# SparkFun_XBee_Arduino_Shield_Qwiic.net
KiCad netlist of a schematic drawn in EAGLE
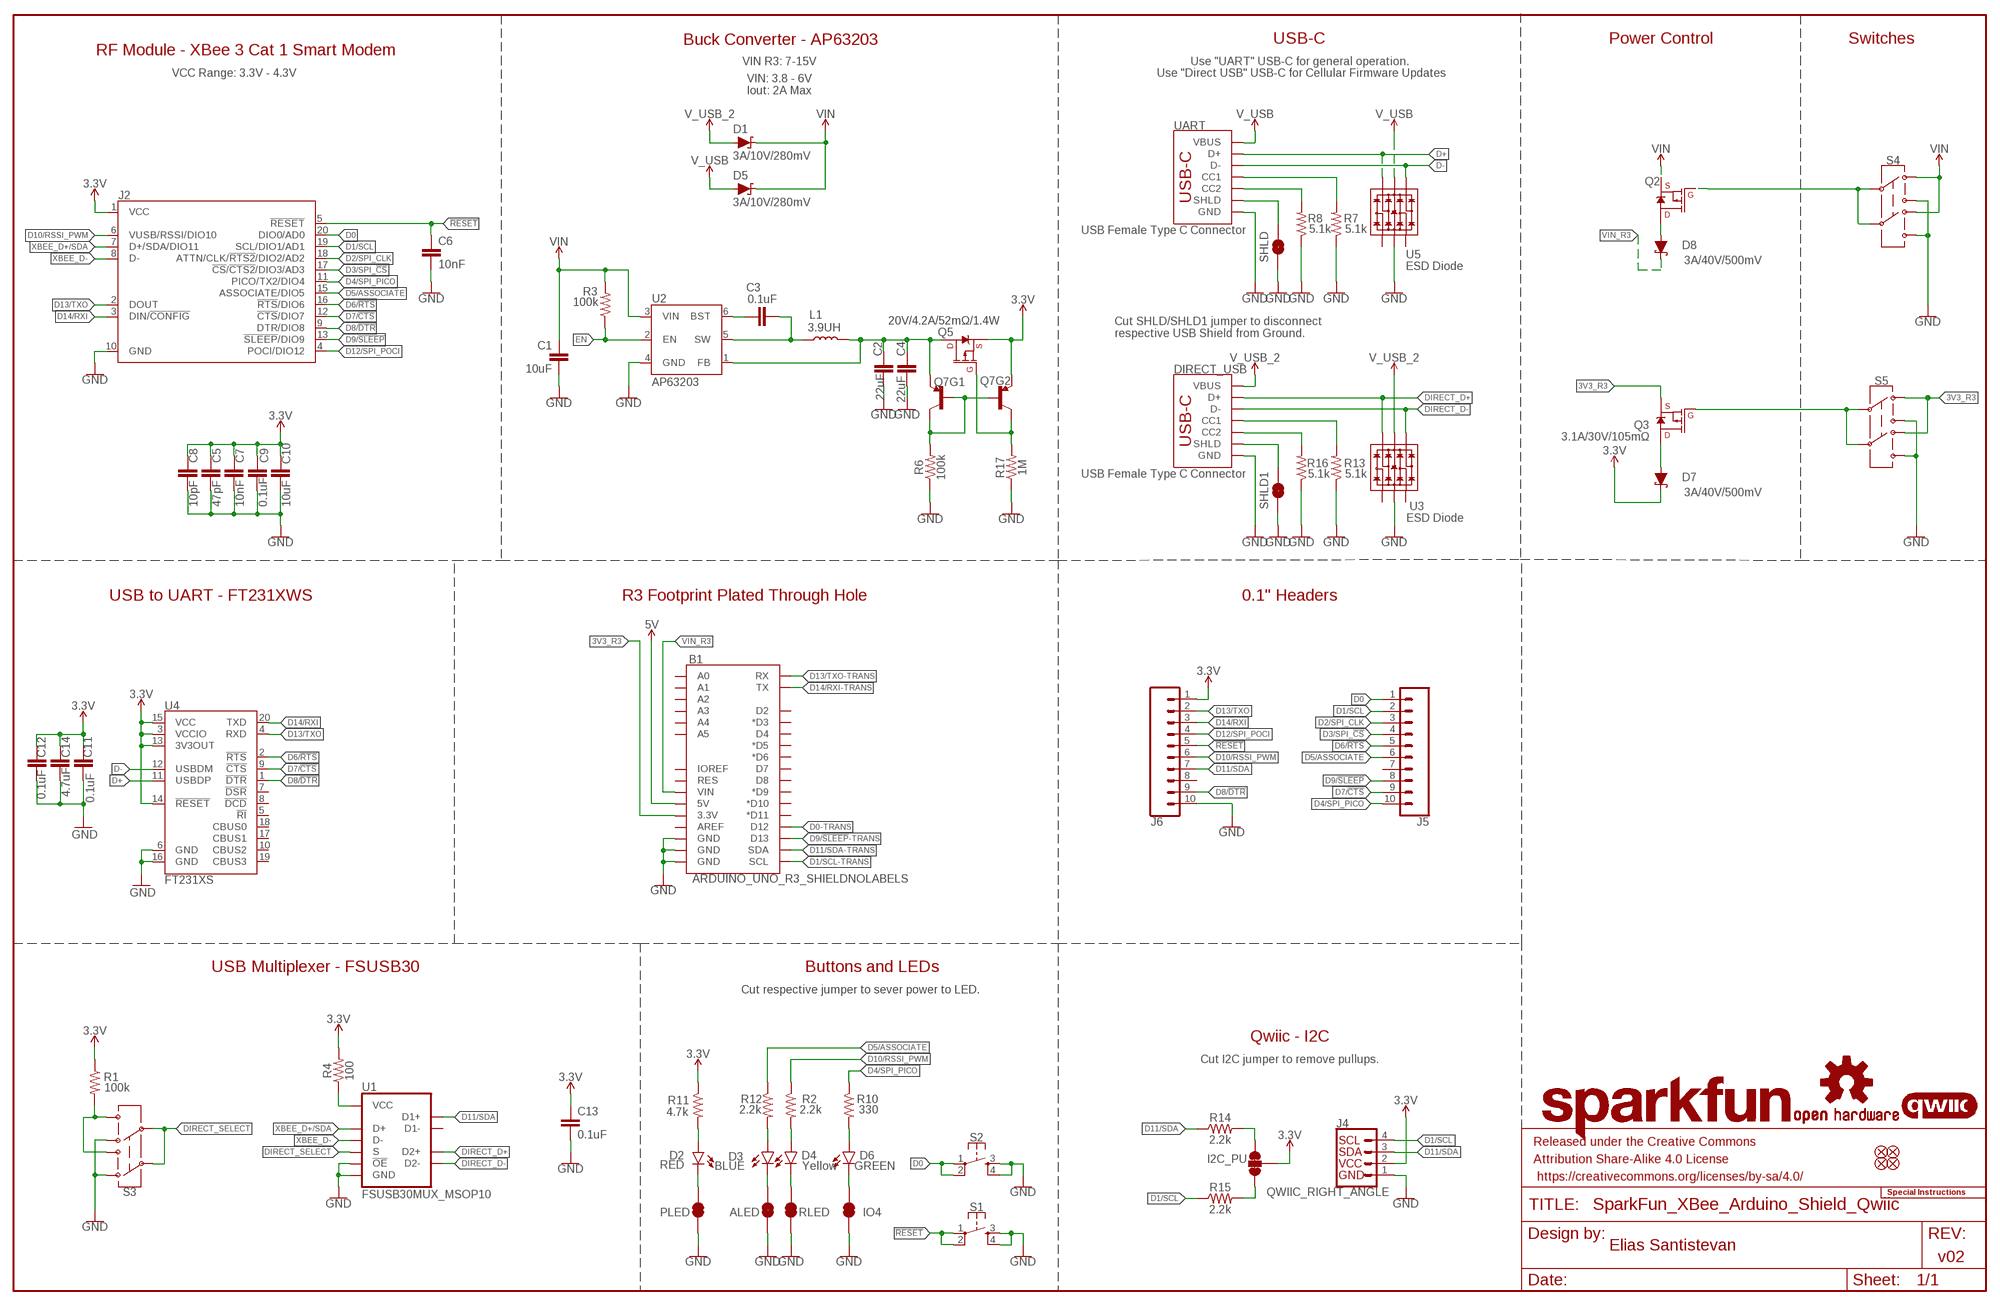
[diagram p0: schematic, sheet 1]

(export (version "E")
  (design (tool "Eeschema 10.0.6"))
  (components
    (comp (ref "ALED")
      (value "JUMPER-SMT_2_NC_TRACE_SILK")
      (footprint "eagle-import:SMT-JUMPER_2_NC_TRACE_SILK")
      (libsource (lib "eagle-import") (part "JUMPER-SMT_2_NC_TRACE_SILK"))
    )
    (comp (ref "B1")
      (value "ARDUINO_UNO_R3_SHIELDNOLABELS")
      (footprint "eagle-import:UNO_R3_SHIELD_NOLABELS")
      (libsource (lib "eagle-import") (part "ARDUINO_UNO_R3_SHIELDNOLABELS"))
    )
    (comp (ref "C1")
      (value "10uF")
      (footprint "eagle-import:1210")
      (libsource (lib "eagle-import") (part "10UF-1210-50V-20%"))
    )
    (comp (ref "C2")
      (value "22uF")
      (footprint "eagle-import:0603")
      (libsource (lib "eagle-import") (part "22UF-0603-6.3V-20%"))
    )
    (comp (ref "C3")
      (value "0.1uF")
      (footprint "eagle-import:0603")
      (libsource (lib "eagle-import") (part "0.1UF-0603-25V-5%"))
    )
    (comp (ref "C4")
      (value "22uF")
      (footprint "eagle-import:0603")
      (libsource (lib "eagle-import") (part "22UF-0603-6.3V-20%"))
    )
    (comp (ref "C5")
      (value "47pF")
      (footprint "eagle-import:0603")
      (libsource (lib "eagle-import") (part "47PF-0603-50V-5%"))
    )
    (comp (ref "C6")
      (value "10nF")
      (footprint "eagle-import:0603")
      (libsource (lib "eagle-import") (part "10NF-0603-50V-10%"))
    )
    (comp (ref "C7")
      (value "10nF")
      (footprint "eagle-import:0603")
      (libsource (lib "eagle-import") (part "10NF-0603-50V-10%"))
    )
    (comp (ref "C8")
      (value "10pF")
      (footprint "eagle-import:0603")
      (libsource (lib "eagle-import") (part "10PF-0603-50V-5%"))
    )
    (comp (ref "C9")
      (value "0.1uF")
      (footprint "eagle-import:0603")
      (libsource (lib "eagle-import") (part "0.1UF-0603-25V-(+80/-20%)"))
    )
    (comp (ref "C10")
      (value "10uF")
      (footprint "eagle-import:0603")
      (libsource (lib "eagle-import") (part "10UF-0603-6.3V-20%"))
    )
    (comp (ref "C11")
      (value "0.1uF")
      (footprint "eagle-import:0603")
      (libsource (lib "eagle-import") (part "0.1UF-0603-25V-(+80/-20%)"))
    )
    (comp (ref "C12")
      (value "0.1uF")
      (footprint "eagle-import:0603")
      (libsource (lib "eagle-import") (part "0.1UF-0603-25V-(+80/-20%)"))
    )
    (comp (ref "C13")
      (value "0.1uF")
      (footprint "eagle-import:0603")
      (libsource (lib "eagle-import") (part "0.1UF-0603-25V-(+80/-20%)"))
    )
    (comp (ref "C14")
      (value "4.7uF")
      (footprint "eagle-import:0603")
      (libsource (lib "eagle-import") (part "4.7UF-0603-6.3V-(10%)"))
    )
    (comp (ref "D1")
      (value "3A/10V/280mV")
      (footprint "eagle-import:SOD-323")
      (libsource (lib "eagle-import") (part "DIODE-SCHOTTKY-BAT60A"))
    )
    (comp (ref "D2")
      (value "RED")
      (footprint "eagle-import:LED-0603")
      (libsource (lib "eagle-import") (part "LED-RED_0603-KB"))
    )
    (comp (ref "D3")
      (value "BLUE")
      (footprint "eagle-import:LED-0603")
      (libsource (lib "eagle-import") (part "LED-BLUE0603"))
    )
    (comp (ref "D4")
      (value "Yellow")
      (footprint "eagle-import:LED-0603")
      (libsource (lib "eagle-import") (part "LED-YELLOW0603"))
    )
    (comp (ref "D5")
      (value "3A/10V/280mV")
      (footprint "eagle-import:SOD-323")
      (libsource (lib "eagle-import") (part "DIODE-SCHOTTKY-BAT60A"))
    )
    (comp (ref "D6")
      (value "GREEN")
      (footprint "eagle-import:LED-0603")
      (libsource (lib "eagle-import") (part "LED-GREEN0603"))
    )
    (comp (ref "D7")
      (value "3A/40V/500mV")
      (footprint "eagle-import:SMA-DIODE")
      (libsource (lib "eagle-import") (part "DIODE-SCHOTTKY-B340A"))
    )
    (comp (ref "D8")
      (value "3A/40V/500mV")
      (footprint "eagle-import:SMA-DIODE")
      (libsource (lib "eagle-import") (part "DIODE-SCHOTTKY-B340A"))
    )
    (comp (ref "DIRECT_USB")
      (value "USB Female Type C Connector")
      (footprint "eagle-import:USB-C-16P-4LAYER-ISOLATED")
      (libsource (lib "eagle-import") (part "USB_C_4-LAYER-ISOLATED"))
    )
    (comp (ref "FD1")
      (value "FIDUCIAL1X2")
      (footprint "eagle-import:FIDUCIAL-1X2")
      (libsource (lib "eagle-import") (part "FIDUCIAL1X2"))
    )
    (comp (ref "FD2")
      (value "FIDUCIAL1X2")
      (footprint "eagle-import:FIDUCIAL-1X2")
      (libsource (lib "eagle-import") (part "FIDUCIAL1X2"))
    )
    (comp (ref "FD3")
      (value "FIDUCIAL1X2")
      (footprint "eagle-import:FIDUCIAL-1X2")
      (libsource (lib "eagle-import") (part "FIDUCIAL1X2"))
    )
    (comp (ref "FD4")
      (value "FIDUCIAL1X2")
      (footprint "eagle-import:FIDUCIAL-1X2")
      (libsource (lib "eagle-import") (part "FIDUCIAL1X2"))
    )
    (comp (ref "FRAME1")
      (value "FRAME-LEDGER")
      (footprint "eagle-import:CREATIVE_COMMONS")
      (libsource (lib "eagle-import") (part "FRAME-LEDGER"))
    )
    (comp (ref "I2C_PU")
      (value "JUMPER-SMT_3_2-NC_TRACE_SILK")
      (footprint "eagle-import:SMT-JUMPER_3_2-NC_TRACE_SILK")
      (libsource (lib "eagle-import") (part "JUMPER-SMT_3_2-NC_TRACE_SILK"))
    )
    (comp (ref "IO4")
      (value "JUMPER-SMT_2_NC_TRACE_SILK")
      (footprint "eagle-import:SMT-JUMPER_2_NC_TRACE_SILK")
      (libsource (lib "eagle-import") (part "JUMPER-SMT_2_NC_TRACE_SILK"))
    )
    (comp (ref "J2")
      (value "XBEE_UPDATEXBEE_SMD")
      (footprint "eagle-import:XBEE3-SMD")
      (libsource (lib "eagle-import") (part "XBEE_UPDATEXBEE_SMD"))
    )
    (comp (ref "J4")
      (value "QWIIC_RIGHT_ANGLE")
      (footprint "eagle-import:JST04_1MM_RA")
      (libsource (lib "eagle-import") (part "QWIIC_CONNECTORJS-1MM"))
    )
    (comp (ref "J5")
      (value "CONN_10NO_SILK_PTH_FEMALE")
      (footprint "eagle-import:1X10_NO_SILK")
      (libsource (lib "eagle-import") (part "CONN_10NO_SILK_PTH_FEMALE"))
    )
    (comp (ref "J6")
      (value "CONN_10NO_SILK_PTH_FEMALE")
      (footprint "eagle-import:1X10_NO_SILK")
      (libsource (lib "eagle-import") (part "CONN_10NO_SILK_PTH_FEMALE"))
    )
    (comp (ref "L1")
      (value "3.9UH")
      (footprint "eagle-import:INDUCTOR_3.9UH")
      (libsource (lib "eagle-import") (part "3.9UH"))
    )
    (comp (ref "LOGO1")
      (value "SFE_LOGO_NAMEBLANK")
      (footprint "eagle-import:BLANK")
      (libsource (lib "eagle-import") (part "SFE_LOGO_NAMEBLANK"))
    )
    (comp (ref "LOGO2")
      (value "OSHW-LOGOS")
      (footprint "eagle-import:OSHW-LOGO-S")
      (libsource (lib "eagle-import") (part "OSHW-LOGOS"))
    )
    (comp (ref "LOGO3")
      (value "QWIIC_LOGO_4MM")
      (footprint "eagle-import:QWIIC_4MM")
      (libsource (lib "eagle-import") (part "QWIIC_LOGO_4MM"))
    )
    (comp (ref "LOGO4")
      (value "SPECIAL_INSTRUCTIONS-ORDERING")
      (footprint "eagle-import:ORDERING_INSTRUCTIONS")
      (libsource (lib "eagle-import") (part "SPECIAL_INSTRUCTIONS-ORDERING"))
    )
    (comp (ref "PLED")
      (value "JUMPER-SMT_2_NC_TRACE_SILK")
      (footprint "eagle-import:SMT-JUMPER_2_NC_TRACE_SILK")
      (libsource (lib "eagle-import") (part "JUMPER-SMT_2_NC_TRACE_SILK"))
    )
    (comp (ref "Q2")
      (value "20V/4.2A/52mΩ/1.4W")
      (footprint "eagle-import:SOT23-3")
      (libsource (lib "eagle-import") (part "MOSFET_PCH-DMG2305UX-7"))
    )
    (comp (ref "Q3")
      (value "3.1A/30V/105mΩ")
      (footprint "eagle-import:SOT23-3")
      (libsource (lib "eagle-import") (part "MOSFET_PCH-DMG2307L"))
    )
    (comp (ref "Q5")
      (value "20V/4.2A/52mΩ/1.4W")
      (footprint "eagle-import:SOT23-3")
      (libsource (lib "eagle-import") (part "MOSFET_PCH-DMG2305UX-7"))
    )
    (comp (ref "Q7")
      (value "TRANS_PNP_DUALSOT-363")
      (footprint "eagle-import:SOT363_PHILIPS")
      (libsource (lib "eagle-import") (part "TRANS_PNP_DUALSOT-363"))
    )
    (comp (ref "R1")
      (value "100k")
      (footprint "eagle-import:0603")
      (libsource (lib "eagle-import") (part "100KOHM-0603-1/10W-1%"))
    )
    (comp (ref "R2")
      (value "2.2k")
      (footprint "eagle-import:0603")
      (libsource (lib "eagle-import") (part "2.2KOHM-0603-1/10W-1%"))
    )
    (comp (ref "R3")
      (value "100k")
      (footprint "eagle-import:0603")
      (libsource (lib "eagle-import") (part "100KOHM-0603-1/10W-1%"))
    )
    (comp (ref "R4")
      (value "100")
      (footprint "eagle-import:0603")
      (libsource (lib "eagle-import") (part "100OHM-0603-1/10W-1%"))
    )
    (comp (ref "R6")
      (value "100k")
      (footprint "eagle-import:0603")
      (libsource (lib "eagle-import") (part "100KOHM-0603-1/10W-1%"))
    )
    (comp (ref "R7")
      (value "5.1k")
      (footprint "eagle-import:0603")
      (libsource (lib "eagle-import") (part "5.1KOHM5.1KOHM-0603-1/10W-1%"))
    )
    (comp (ref "R8")
      (value "5.1k")
      (footprint "eagle-import:0603")
      (libsource (lib "eagle-import") (part "5.1KOHM5.1KOHM-0603-1/10W-1%"))
    )
    (comp (ref "R10")
      (value "330")
      (footprint "eagle-import:0603")
      (libsource (lib "eagle-import") (part "330OHM-0603-1/10W-1%"))
    )
    (comp (ref "R11")
      (value "4.7k")
      (footprint "eagle-import:0603")
      (libsource (lib "eagle-import") (part "4.7KOHM-0603-1/10W-1%"))
    )
    (comp (ref "R12")
      (value "2.2k")
      (footprint "eagle-import:0603")
      (libsource (lib "eagle-import") (part "2.2KOHM-0603-1/10W-1%"))
    )
    (comp (ref "R13")
      (value "5.1k")
      (footprint "eagle-import:0603")
      (libsource (lib "eagle-import") (part "5.1KOHM5.1KOHM-0603-1/10W-1%"))
    )
    (comp (ref "R14")
      (value "2.2k")
      (footprint "eagle-import:0603")
      (libsource (lib "eagle-import") (part "2.2KOHM-0603-1/10W-1%"))
    )
    (comp (ref "R15")
      (value "2.2k")
      (footprint "eagle-import:0603")
      (libsource (lib "eagle-import") (part "2.2KOHM-0603-1/10W-1%"))
    )
    (comp (ref "R16")
      (value "5.1k")
      (footprint "eagle-import:0603")
      (libsource (lib "eagle-import") (part "5.1KOHM5.1KOHM-0603-1/10W-1%"))
    )
    (comp (ref "R17")
      (value "1M")
      (footprint "eagle-import:0603")
      (libsource (lib "eagle-import") (part "1MOHM-0603-1/4W-5%"))
    )
    (comp (ref "RLED")
      (value "JUMPER-SMT_2_NC_TRACE_SILK")
      (footprint "eagle-import:SMT-JUMPER_2_NC_TRACE_SILK")
      (libsource (lib "eagle-import") (part "JUMPER-SMT_2_NC_TRACE_SILK"))
    )
    (comp (ref "S1")
      (value "MOMENTARY-SWITCH-SPST-2-SMD-5.2MM-TALL")
      (footprint "eagle-import:TACTILE_SWITCH_SMD_5.2MM")
      (libsource (lib "eagle-import") (part "MOMENTARY-SWITCH-SPST-2-SMD-5.2MM-TALL"))
    )
    (comp (ref "S2")
      (value "MOMENTARY-SWITCH-SPST-2-SMD-5.2MM-TALL")
      (footprint "eagle-import:TACTILE_SWITCH_SMD_5.2MM")
      (libsource (lib "eagle-import") (part "MOMENTARY-SWITCH-SPST-2-SMD-5.2MM-TALL"))
    )
    (comp (ref "S3")
      (value "SWITCH-DPDT-SMD-AYZ0202")
      (footprint "eagle-import:SWITCH_DPDT_SMD_AYZ0202")
      (libsource (lib "eagle-import") (part "SWITCH-DPDT-SMD-AYZ0202"))
    )
    (comp (ref "S4")
      (value "SWITCH-DPDT-SMD-AYZ0202")
      (footprint "eagle-import:SWITCH_DPDT_SMD_AYZ0202")
      (libsource (lib "eagle-import") (part "SWITCH-DPDT-SMD-AYZ0202"))
    )
    (comp (ref "S5")
      (value "SWITCH-DPDT-SMD-AYZ0202")
      (footprint "eagle-import:SWITCH_DPDT_SMD_AYZ0202")
      (libsource (lib "eagle-import") (part "SWITCH-DPDT-SMD-AYZ0202"))
    )
    (comp (ref "SHLD")
      (value "JUMPER-SMT_2_NC_TRACE_SILK")
      (footprint "eagle-import:SMT-JUMPER_2_NC_TRACE_SILK")
      (libsource (lib "eagle-import") (part "JUMPER-SMT_2_NC_TRACE_SILK"))
    )
    (comp (ref "SHLD1")
      (value "JUMPER-SMT_2_NC_TRACE_SILK")
      (footprint "eagle-import:SMT-JUMPER_2_NC_TRACE_SILK")
      (libsource (lib "eagle-import") (part "JUMPER-SMT_2_NC_TRACE_SILK"))
    )
    (comp (ref "U1")
      (value "FSUSB30MUX_MSOP10")
      (footprint "eagle-import:MSOP10")
      (libsource (lib "eagle-import") (part "FSUSB30MUX_MSOP10"))
    )
    (comp (ref "U2")
      (value "AP63203")
      (footprint "eagle-import:SOT23-6")
      (libsource (lib "eagle-import") (part "AP63203"))
    )
    (comp (ref "U3")
      (value "ESD Diode")
      (footprint "eagle-import:SOT-23-6")
      (libsource (lib "eagle-import") (part "TVS_DIODE_ARRAY_DT1042-04SO-7"))
    )
    (comp (ref "U4")
      (value "FT231XS")
      (footprint "eagle-import:SSOP20_L")
      (libsource (lib "eagle-import") (part "FT231XS"))
    )
    (comp (ref "U5")
      (value "ESD Diode")
      (footprint "eagle-import:SOT-23-6")
      (libsource (lib "eagle-import") (part "TVS_DIODE_ARRAY_DT1042-04SO-7"))
    )
    (comp (ref "UART")
      (value "USB Female Type C Connector")
      (footprint "eagle-import:USB-C-16P-4LAYER-ISOLATED")
      (libsource (lib "eagle-import") (part "USB_C_4-LAYER-ISOLATED"))
    )
  )
  (nets
    (net (code "1") (name "/D3{slash}SPI_~{CS}") (class "Default")
      (node (ref "J2") (pin "17") (pinfunction "~{CS}/~{CTS2}/DIO3/AD3_17") (pintype "bidirectional"))
      (node (ref "J5") (pin "4") (pinfunction "4_4") (pintype "passive"))
    )
    (net (code "2") (name "/D6{slash}~{RTS}") (class "Default")
      (node (ref "J2") (pin "16") (pinfunction "~{RTS}/DIO6_16") (pintype "input"))
      (node (ref "J5") (pin "5") (pinfunction "5_5") (pintype "passive"))
      (node (ref "U4") (pin "2") (pinfunction "~{RTS}_2") (pintype "bidirectional"))
    )
    (net (code "3") (name "/D7{slash}~{CTS}") (class "Default")
      (node (ref "J2") (pin "12") (pinfunction "~{CTS}/DIO7_12") (pintype "output"))
      (node (ref "J5") (pin "9") (pinfunction "9_9") (pintype "passive"))
      (node (ref "U4") (pin "9") (pinfunction "~{CTS}_9") (pintype "bidirectional"))
    )
    (net (code "4") (name "/D8{slash}~{DTR}") (class "Default")
      (node (ref "J2") (pin "9") (pinfunction "DTR/DIO8_9") (pintype "bidirectional"))
      (node (ref "J6") (pin "9") (pinfunction "9_9") (pintype "passive"))
      (node (ref "U4") (pin "1") (pinfunction "~{DTR}_1") (pintype "bidirectional"))
    )
    (net (code "5") (name "/D9{slash}~{SLEEP}") (class "Default")
      (node (ref "J2") (pin "13") (pinfunction "~{SLEEP}/DIO9_13") (pintype "bidirectional"))
      (node (ref "J5") (pin "8") (pinfunction "8_8") (pintype "passive"))
    )
    (net (code "6") (name "/D9{slash}~{SLEEP}-TRANS") (class "Default")
      (node (ref "B1") (pin "D13") (pinfunction "D13_D13") (pintype "bidirectional"))
    )
    (net (code "7") (name "/~{RESET}") (class "Default")
      (node (ref "C6") (pin "1") (pinfunction "1_1") (pintype "passive"))
      (node (ref "J2") (pin "5") (pinfunction "~{RESET}_5") (pintype "input"))
      (node (ref "J6") (pin "5") (pinfunction "5_5") (pintype "passive"))
      (node (ref "S1") (pin "1") (pinfunction "1_1") (pintype "passive"))
      (node (ref "S1") (pin "2") (pinfunction "2_2") (pintype "passive"))
    )
    (net (code "8") (name "3.3V") (class "Default")
      (node (ref "C10") (pin "1") (pinfunction "1_1") (pintype "passive"))
      (node (ref "C11") (pin "1") (pinfunction "1_1") (pintype "passive"))
      (node (ref "C12") (pin "1") (pinfunction "1_1") (pintype "passive"))
      (node (ref "C13") (pin "1") (pinfunction "1_1") (pintype "passive"))
      (node (ref "C14") (pin "1") (pinfunction "1_1") (pintype "passive"))
      (node (ref "C5") (pin "1") (pinfunction "1_1") (pintype "passive"))
      (node (ref "C7") (pin "1") (pinfunction "1_1") (pintype "passive"))
      (node (ref "C8") (pin "1") (pinfunction "1_1") (pintype "passive"))
      (node (ref "C9") (pin "1") (pinfunction "1_1") (pintype "passive"))
      (node (ref "D7") (pin "C") (pinfunction "C_C") (pintype "passive"))
      (node (ref "I2C_PU") (pin "2") (pinfunction "2_2") (pintype "passive"))
      (node (ref "J2") (pin "1") (pinfunction "VCC_1") (pintype "power_in"))
      (node (ref "J4") (pin "2") (pinfunction "2_2") (pintype "power_in"))
      (node (ref "J6") (pin "1") (pinfunction "1_1") (pintype "passive"))
      (node (ref "Q5") (pin "2") (pinfunction "S_2") (pintype "bidirectional"))
      (node (ref "Q7") (pin "4") (pinfunction "E_4") (pintype "passive"))
      (node (ref "R1") (pin "1") (pinfunction "1_1") (pintype "passive"))
      (node (ref "R11") (pin "1") (pinfunction "1_1") (pintype "passive"))
      (node (ref "R4") (pin "2") (pinfunction "2_2") (pintype "passive"))
      (node (ref "U4") (pin "13") (pinfunction "3V3OUT_13") (pintype "bidirectional"))
      (node (ref "U4") (pin "14") (pinfunction "~{RESET}_14") (pintype "bidirectional"))
      (node (ref "U4") (pin "15") (pinfunction "VCC_15") (pintype "bidirectional"))
      (node (ref "U4") (pin "3") (pinfunction "VCCIO_3") (pintype "bidirectional"))
    )
    (net (code "9") (name "3V3_R3") (class "Default")
      (node (ref "B1") (pin "3.3V") (pinfunction "3.3V_3.3V") (pintype "bidirectional"))
      (node (ref "Q3") (pin "2") (pinfunction "S_2") (pintype "bidirectional"))
      (node (ref "S5") (pin "3") (pinfunction "3_3") (pintype "bidirectional"))
      (node (ref "S5") (pin "6") (pinfunction "6_6") (pintype "bidirectional"))
    )
    (net (code "10") (name "5V") (class "Default")
      (node (ref "B1") (pin "5V") (pinfunction "5V_5V") (pintype "bidirectional"))
    )
    (net (code "11") (name "D+") (class "Default")
      (node (ref "U4") (pin "11") (pinfunction "USBDP_11") (pintype "bidirectional"))
      (node (ref "U5") (pin "6") (pinfunction "IO4_6") (pintype "bidirectional"))
      (node (ref "UART") (pin "A6") (pinfunction "D+_A6") (pintype "bidirectional"))
      (node (ref "UART") (pin "B6") (pinfunction "D+_B6") (pintype "bidirectional"))
    )
    (net (code "12") (name "D-") (class "Default")
      (node (ref "U4") (pin "12") (pinfunction "USBDM_12") (pintype "bidirectional"))
      (node (ref "U5") (pin "4") (pinfunction "IO3_4") (pintype "bidirectional"))
      (node (ref "UART") (pin "A7") (pinfunction "D-_A7") (pintype "bidirectional"))
      (node (ref "UART") (pin "B7") (pinfunction "D-_B7") (pintype "bidirectional"))
    )
    (net (code "13") (name "D0") (class "Default")
      (node (ref "J2") (pin "20") (pinfunction "DIO0/AD0_20") (pintype "bidirectional"))
      (node (ref "J5") (pin "1") (pinfunction "1_1") (pintype "passive"))
      (node (ref "S2") (pin "1") (pinfunction "1_1") (pintype "passive"))
      (node (ref "S2") (pin "2") (pinfunction "2_2") (pintype "passive"))
    )
    (net (code "14") (name "D0-TRANS") (class "Default")
      (node (ref "B1") (pin "D12") (pinfunction "D12_D12") (pintype "bidirectional"))
    )
    (net (code "15") (name "D1{slash}SCL") (class "Default")
      (node (ref "J2") (pin "19") (pinfunction "SCL/DIO1/AD1_19") (pintype "bidirectional"))
      (node (ref "J4") (pin "4") (pinfunction "4_4") (pintype "passive"))
      (node (ref "J5") (pin "2") (pinfunction "2_2") (pintype "passive"))
      (node (ref "R15") (pin "1") (pinfunction "1_1") (pintype "passive"))
    )
    (net (code "16") (name "D1{slash}SCL-TRANS") (class "Default")
      (node (ref "B1") (pin "SCL") (pinfunction "SCL_SCL") (pintype "bidirectional"))
    )
    (net (code "17") (name "D2{slash}SPI_CLK") (class "Default")
      (node (ref "J2") (pin "18") (pinfunction "ATTN/CLK/~{RTS2}/DIO2/AD2_18") (pintype "bidirectional"))
      (node (ref "J5") (pin "3") (pinfunction "3_3") (pintype "passive"))
    )
    (net (code "18") (name "D4{slash}SPI_PICO") (class "Default")
      (node (ref "J2") (pin "11") (pinfunction "PICO/TX2/DIO4_11") (pintype "bidirectional"))
      (node (ref "J5") (pin "10") (pinfunction "10_10") (pintype "passive"))
      (node (ref "R10") (pin "1") (pinfunction "1_1") (pintype "passive"))
    )
    (net (code "19") (name "D5{slash}ASSOCIATE") (class "Default")
      (node (ref "J2") (pin "15") (pinfunction "ASSOCIATE/DIO5_15") (pintype "bidirectional"))
      (node (ref "J5") (pin "6") (pinfunction "6_6") (pintype "passive"))
      (node (ref "R12") (pin "1") (pinfunction "1_1") (pintype "passive"))
    )
    (net (code "20") (name "D10{slash}RSSI_PWM") (class "Default")
      (node (ref "J2") (pin "6") (pinfunction "VUSB/RSSI/DIO10_6") (pintype "bidirectional"))
      (node (ref "J6") (pin "6") (pinfunction "6_6") (pintype "passive"))
      (node (ref "R2") (pin "1") (pinfunction "1_1") (pintype "passive"))
    )
    (net (code "21") (name "D11{slash}SDA") (class "Default")
      (node (ref "J4") (pin "3") (pinfunction "3_3") (pintype "passive"))
      (node (ref "J6") (pin "7") (pinfunction "7_7") (pintype "passive"))
      (node (ref "R14") (pin "1") (pinfunction "1_1") (pintype "passive"))
      (node (ref "U1") (pin "2") (pinfunction "D1+_2") (pintype "bidirectional"))
    )
    (net (code "22") (name "D11{slash}SDA-TRANS") (class "Default")
      (node (ref "B1") (pin "SDA") (pinfunction "SDA_SDA") (pintype "bidirectional"))
    )
    (net (code "23") (name "D12{slash}SPI_POCI") (class "Default")
      (node (ref "J2") (pin "4") (pinfunction "POCI/DIO12_4") (pintype "bidirectional"))
      (node (ref "J6") (pin "4") (pinfunction "4_4") (pintype "passive"))
    )
    (net (code "24") (name "D13{slash}TXO") (class "Default")
      (node (ref "J2") (pin "2") (pinfunction "DOUT_2") (pintype "output"))
      (node (ref "J6") (pin "2") (pinfunction "2_2") (pintype "passive"))
      (node (ref "U4") (pin "4") (pinfunction "RXD_4") (pintype "bidirectional"))
    )
    (net (code "25") (name "D13{slash}TXO-TRANS") (class "Default")
      (node (ref "B1") (pin "RX") (pinfunction "RX_RX") (pintype "bidirectional"))
    )
    (net (code "26") (name "D14{slash}RXI") (class "Default")
      (node (ref "J2") (pin "3") (pinfunction "DIN/~{CONFIG}_3") (pintype "input"))
      (node (ref "J6") (pin "3") (pinfunction "3_3") (pintype "passive"))
      (node (ref "U4") (pin "20") (pinfunction "TXD_20") (pintype "bidirectional"))
    )
    (net (code "27") (name "D14{slash}RXI-TRANS") (class "Default")
      (node (ref "B1") (pin "TX") (pinfunction "TX_TX") (pintype "bidirectional"))
    )
    (net (code "28") (name "DIRECT_D+") (class "Default")
      (node (ref "DIRECT_USB") (pin "A6") (pinfunction "D+_A6") (pintype "bidirectional"))
      (node (ref "DIRECT_USB") (pin "B6") (pinfunction "D+_B6") (pintype "bidirectional"))
      (node (ref "U1") (pin "3") (pinfunction "D2+_3") (pintype "bidirectional"))
      (node (ref "U3") (pin "6") (pinfunction "IO4_6") (pintype "bidirectional"))
    )
    (net (code "29") (name "DIRECT_D-") (class "Default")
      (node (ref "DIRECT_USB") (pin "A7") (pinfunction "D-_A7") (pintype "bidirectional"))
      (node (ref "DIRECT_USB") (pin "B7") (pinfunction "D-_B7") (pintype "bidirectional"))
      (node (ref "U1") (pin "7") (pinfunction "D2-_7") (pintype "bidirectional"))
      (node (ref "U3") (pin "4") (pinfunction "IO3_4") (pintype "bidirectional"))
    )
    (net (code "30") (name "DIRECT_SELECT") (class "Default")
      (node (ref "S3") (pin "2") (pinfunction "2_2") (pintype "bidirectional"))
      (node (ref "S3") (pin "5") (pinfunction "5_5") (pintype "bidirectional"))
      (node (ref "U1") (pin "1") (pinfunction "S_1") (pintype "bidirectional"))
    )
    (net (code "31") (name "EN") (class "Default")
      (node (ref "R3") (pin "1") (pinfunction "1_1") (pintype "passive"))
      (node (ref "U2") (pin "2") (pinfunction "EN_2") (pintype "bidirectional"))
    )
    (net (code "32") (name "GND") (class "Default")
      (node (ref "ALED") (pin "1") (pinfunction "1_1") (pintype "passive"))
      (node (ref "B1") (pin "GND@0") (pinfunction "GND_GND@0") (pintype "bidirectional"))
      (node (ref "B1") (pin "GND@1") (pinfunction "GND_GND@1") (pintype "bidirectional"))
      (node (ref "B1") (pin "GND@2") (pinfunction "GND_GND@2") (pintype "bidirectional"))
      (node (ref "C1") (pin "2") (pinfunction "2_2") (pintype "passive"))
      (node (ref "C10") (pin "2") (pinfunction "2_2") (pintype "passive"))
      (node (ref "C11") (pin "2") (pinfunction "2_2") (pintype "passive"))
      (node (ref "C12") (pin "2") (pinfunction "2_2") (pintype "passive"))
      (node (ref "C13") (pin "2") (pinfunction "2_2") (pintype "passive"))
      (node (ref "C14") (pin "2") (pinfunction "2_2") (pintype "passive"))
      (node (ref "C2") (pin "2") (pinfunction "2_2") (pintype "passive"))
      (node (ref "C4") (pin "2") (pinfunction "2_2") (pintype "passive"))
      (node (ref "C5") (pin "2") (pinfunction "2_2") (pintype "passive"))
      (node (ref "C6") (pin "2") (pinfunction "2_2") (pintype "passive"))
      (node (ref "C7") (pin "2") (pinfunction "2_2") (pintype "passive"))
      (node (ref "C8") (pin "2") (pinfunction "2_2") (pintype "passive"))
      (node (ref "C9") (pin "2") (pinfunction "2_2") (pintype "passive"))
      (node (ref "DIRECT_USB") (pin "GND") (pinfunction "GND_GND") (pintype "bidirectional"))
      (node (ref "DIRECT_USB") (pin "GND2") (pinfunction "GND_GND2") (pintype "bidirectional"))
      (node (ref "IO4") (pin "1") (pinfunction "1_1") (pintype "passive"))
      (node (ref "J2") (pin "10") (pinfunction "GND_10") (pintype "power_in"))
      (node (ref "J4") (pin "1") (pinfunction "1_1") (pintype "power_in"))
      (node (ref "J6") (pin "10") (pinfunction "10_10") (pintype "passive"))
      (node (ref "PLED") (pin "1") (pinfunction "1_1") (pintype "passive"))
      (node (ref "R13") (pin "1") (pinfunction "1_1") (pintype "passive"))
      (node (ref "R16") (pin "1") (pinfunction "1_1") (pintype "passive"))
      (node (ref "R17") (pin "1") (pinfunction "1_1") (pintype "passive"))
      (node (ref "R6") (pin "1") (pinfunction "1_1") (pintype "passive"))
      (node (ref "R7") (pin "1") (pinfunction "1_1") (pintype "passive"))
      (node (ref "R8") (pin "1") (pinfunction "1_1") (pintype "passive"))
      (node (ref "RLED") (pin "1") (pinfunction "1_1") (pintype "passive"))
      (node (ref "S1") (pin "3") (pinfunction "3_3") (pintype "passive"))
      (node (ref "S1") (pin "4") (pinfunction "4_4") (pintype "passive"))
      (node (ref "S2") (pin "3") (pinfunction "3_3") (pintype "passive"))
      (node (ref "S2") (pin "4") (pinfunction "4_4") (pintype "passive"))
      (node (ref "S3") (pin "3") (pinfunction "3_3") (pintype "bidirectional"))
      (node (ref "S3") (pin "6") (pinfunction "6_6") (pintype "bidirectional"))
      (node (ref "S4") (pin "1") (pinfunction "1_1") (pintype "bidirectional"))
      (node (ref "S4") (pin "4") (pinfunction "4_4") (pintype "bidirectional"))
      (node (ref "S5") (pin "1") (pinfunction "1_1") (pintype "bidirectional"))
      (node (ref "S5") (pin "4") (pinfunction "4_4") (pintype "bidirectional"))
      (node (ref "SHLD") (pin "1") (pinfunction "1_1") (pintype "passive"))
      (node (ref "SHLD1") (pin "1") (pinfunction "1_1") (pintype "passive"))
      (node (ref "U1") (pin "5") (pinfunction "GND_5") (pintype "bidirectional"))
      (node (ref "U1") (pin "9") (pinfunction "~{OE}_9") (pintype "bidirectional"))
      (node (ref "U2") (pin "4") (pinfunction "GND_4") (pintype "bidirectional"))
      (node (ref "U3") (pin "2") (pinfunction "VSS_2") (pintype "bidirectional"))
      (node (ref "U4") (pin "16") (pinfunction "GND_16") (pintype "bidirectional"))
      (node (ref "U4") (pin "6") (pinfunction "GND_6") (pintype "bidirectional"))
      (node (ref "U5") (pin "2") (pinfunction "VSS_2") (pintype "bidirectional"))
      (node (ref "UART") (pin "GND") (pinfunction "GND_GND") (pintype "bidirectional"))
      (node (ref "UART") (pin "GND2") (pinfunction "GND_GND2") (pintype "bidirectional"))
    )
    (net (code "33") (name "Net-(ALED-Pad2)") (class "Default")
      (node (ref "ALED") (pin "2") (pinfunction "2_2") (pintype "passive"))
      (node (ref "D3") (pin "C") (pinfunction "C_C") (pintype "passive"))
    )
    (net (code "34") (name "Net-(D2-PadA)") (class "Default")
      (node (ref "D2") (pin "A") (pinfunction "A_A") (pintype "passive"))
      (node (ref "R11") (pin "2") (pinfunction "2_2") (pintype "passive"))
    )
    (net (code "35") (name "Net-(D2-PadC)") (class "Default")
      (node (ref "D2") (pin "C") (pinfunction "C_C") (pintype "passive"))
      (node (ref "PLED") (pin "2") (pinfunction "2_2") (pintype "passive"))
    )
    (net (code "36") (name "Net-(D3-PadA)") (class "Default")
      (node (ref "D3") (pin "A") (pinfunction "A_A") (pintype "passive"))
      (node (ref "R12") (pin "2") (pinfunction "2_2") (pintype "passive"))
    )
    (net (code "37") (name "Net-(D4-PadA)") (class "Default")
      (node (ref "D4") (pin "A") (pinfunction "A_A") (pintype "passive"))
      (node (ref "R2") (pin "2") (pinfunction "2_2") (pintype "passive"))
    )
    (net (code "38") (name "Net-(D4-PadC)") (class "Default")
      (node (ref "D4") (pin "C") (pinfunction "C_C") (pintype "passive"))
      (node (ref "RLED") (pin "2") (pinfunction "2_2") (pintype "passive"))
    )
    (net (code "39") (name "Net-(D6-PadA)") (class "Default")
      (node (ref "D6") (pin "A") (pinfunction "A_A") (pintype "passive"))
      (node (ref "R10") (pin "2") (pinfunction "2_2") (pintype "passive"))
    )
    (net (code "40") (name "Net-(D6-PadC)") (class "Default")
      (node (ref "D6") (pin "C") (pinfunction "C_C") (pintype "passive"))
      (node (ref "IO4") (pin "2") (pinfunction "2_2") (pintype "passive"))
    )
    (net (code "41") (name "Net-(DIRECT_USB-CC1)") (class "Default")
      (node (ref "DIRECT_USB") (pin "A5") (pinfunction "CC1_A5") (pintype "bidirectional"))
      (node (ref "R13") (pin "2") (pinfunction "2_2") (pintype "passive"))
    )
    (net (code "42") (name "Net-(DIRECT_USB-CC2)") (class "Default")
      (node (ref "DIRECT_USB") (pin "B5") (pinfunction "CC2_B5") (pintype "bidirectional"))
      (node (ref "R16") (pin "2") (pinfunction "2_2") (pintype "passive"))
    )
    (net (code "43") (name "Net-(DIRECT_USB-SHLD-PadSHLD1)") (class "Default")
      (node (ref "DIRECT_USB") (pin "SHLD1") (pinfunction "SHLD_SHLD1") (pintype "bidirectional"))
      (node (ref "DIRECT_USB") (pin "SHLD2") (pinfunction "SHLD_SHLD2") (pintype "bidirectional"))
      (node (ref "DIRECT_USB") (pin "SHLD3") (pinfunction "SHLD_SHLD3") (pintype "bidirectional"))
      (node (ref "DIRECT_USB") (pin "SHLD4") (pinfunction "SHLD_SHLD4") (pintype "bidirectional"))
      (node (ref "DIRECT_USB") (pin "SHLD5") (pinfunction "SHLD_SHLD5") (pintype "bidirectional"))
      (node (ref "DIRECT_USB") (pin "SHLD6") (pinfunction "SHLD_SHLD6") (pintype "bidirectional"))
      (node (ref "DIRECT_USB") (pin "SHLD7") (pinfunction "SHLD_SHLD7") (pintype "bidirectional"))
      (node (ref "DIRECT_USB") (pin "SHLD8") (pinfunction "SHLD_SHLD8") (pintype "bidirectional"))
      (node (ref "SHLD1") (pin "2") (pinfunction "2_2") (pintype "passive"))
    )
    (net (code "44") (name "Net-(I2C_PU-Pad1)") (class "Default")
      (node (ref "I2C_PU") (pin "1") (pinfunction "1_1") (pintype "passive"))
      (node (ref "R15") (pin "2") (pinfunction "2_2") (pintype "passive"))
    )
    (net (code "45") (name "Net-(I2C_PU-Pad3)") (class "Default")
      (node (ref "I2C_PU") (pin "3") (pinfunction "3_3") (pintype "passive"))
      (node (ref "R14") (pin "2") (pinfunction "2_2") (pintype "passive"))
    )
    (net (code "46") (name "Net-(L1-1)") (class "Default")
      (node (ref "C3") (pin "2") (pinfunction "2_2") (pintype "passive"))
      (node (ref "L1") (pin "P$1") (pinfunction "1_P$1") (pintype "passive"))
      (node (ref "U2") (pin "5") (pinfunction "SW_5") (pintype "bidirectional"))
    )
    (net (code "47") (name "Net-(L1-2)") (class "Default")
      (node (ref "C2") (pin "1") (pinfunction "1_1") (pintype "passive"))
      (node (ref "C4") (pin "1") (pinfunction "1_1") (pintype "passive"))
      (node (ref "L1") (pin "P$2") (pinfunction "2_P$2") (pintype "passive"))
      (node (ref "Q5") (pin "3") (pinfunction "D_3") (pintype "bidirectional"))
      (node (ref "Q7") (pin "1") (pinfunction "E_1") (pintype "passive"))
      (node (ref "U2") (pin "1") (pinfunction "FB_1") (pintype "bidirectional"))
    )
    (net (code "48") (name "Net-(Q2-D)") (class "Default")
      (node (ref "D8") (pin "A") (pinfunction "A_A") (pintype "passive"))
      (node (ref "Q2") (pin "3") (pinfunction "D_3") (pintype "bidirectional"))
    )
    (net (code "49") (name "Net-(Q2-G)") (class "Default")
      (node (ref "Q2") (pin "1") (pinfunction "G_1") (pintype "bidirectional"))
      (node (ref "S4") (pin "2") (pinfunction "2_2") (pintype "bidirectional"))
      (node (ref "S4") (pin "5") (pinfunction "5_5") (pintype "bidirectional"))
    )
    (net (code "50") (name "Net-(Q3-D)") (class "Default")
      (node (ref "D7") (pin "A") (pinfunction "A_A") (pintype "passive"))
      (node (ref "Q3") (pin "3") (pinfunction "D_3") (pintype "bidirectional"))
    )
    (net (code "51") (name "Net-(Q3-G)") (class "Default")
      (node (ref "Q3") (pin "1") (pinfunction "G_1") (pintype "bidirectional"))
      (node (ref "S5") (pin "2") (pinfunction "2_2") (pintype "bidirectional"))
      (node (ref "S5") (pin "5") (pinfunction "5_5") (pintype "bidirectional"))
    )
    (net (code "52") (name "Net-(Q5-G)") (class "Default")
      (node (ref "Q5") (pin "1") (pinfunction "G_1") (pintype "bidirectional"))
      (node (ref "Q7") (pin "3") (pinfunction "C_3") (pintype "passive"))
      (node (ref "R17") (pin "2") (pinfunction "2_2") (pintype "passive"))
    )
    (net (code "53") (name "Net-(Q7A-B)") (class "Default")
      (node (ref "Q7") (pin "2") (pinfunction "B_2") (pintype "passive"))
      (node (ref "Q7") (pin "5") (pinfunction "B_5") (pintype "passive"))
      (node (ref "Q7") (pin "6") (pinfunction "C_6") (pintype "passive"))
      (node (ref "R6") (pin "2") (pinfunction "2_2") (pintype "passive"))
    )
    (net (code "54") (name "Net-(R1-Pad2)") (class "Default")
      (node (ref "R1") (pin "2") (pinfunction "2_2") (pintype "passive"))
      (node (ref "S3") (pin "1") (pinfunction "1_1") (pintype "bidirectional"))
      (node (ref "S3") (pin "4") (pinfunction "4_4") (pintype "bidirectional"))
    )
    (net (code "55") (name "Net-(SHLD-Pad2)") (class "Default")
      (node (ref "SHLD") (pin "2") (pinfunction "2_2") (pintype "passive"))
      (node (ref "UART") (pin "SHLD1") (pinfunction "SHLD_SHLD1") (pintype "bidirectional"))
      (node (ref "UART") (pin "SHLD2") (pinfunction "SHLD_SHLD2") (pintype "bidirectional"))
      (node (ref "UART") (pin "SHLD3") (pinfunction "SHLD_SHLD3") (pintype "bidirectional"))
      (node (ref "UART") (pin "SHLD4") (pinfunction "SHLD_SHLD4") (pintype "bidirectional"))
      (node (ref "UART") (pin "SHLD5") (pinfunction "SHLD_SHLD5") (pintype "bidirectional"))
      (node (ref "UART") (pin "SHLD6") (pinfunction "SHLD_SHLD6") (pintype "bidirectional"))
      (node (ref "UART") (pin "SHLD7") (pinfunction "SHLD_SHLD7") (pintype "bidirectional"))
      (node (ref "UART") (pin "SHLD8") (pinfunction "SHLD_SHLD8") (pintype "bidirectional"))
    )
    (net (code "56") (name "Net-(U1-VCC)") (class "Default")
      (node (ref "R4") (pin "1") (pinfunction "1_1") (pintype "passive"))
      (node (ref "U1") (pin "10") (pinfunction "VCC_10") (pintype "bidirectional"))
    )
    (net (code "57") (name "Net-(U2-BST)") (class "Default")
      (node (ref "C3") (pin "1") (pinfunction "1_1") (pintype "passive"))
      (node (ref "U2") (pin "6") (pinfunction "BST_6") (pintype "bidirectional"))
    )
    (net (code "58") (name "Net-(UART-CC1)") (class "Default")
      (node (ref "R7") (pin "2") (pinfunction "2_2") (pintype "passive"))
      (node (ref "UART") (pin "A5") (pinfunction "CC1_A5") (pintype "bidirectional"))
    )
    (net (code "59") (name "Net-(UART-CC2)") (class "Default")
      (node (ref "R8") (pin "2") (pinfunction "2_2") (pintype "passive"))
      (node (ref "UART") (pin "B5") (pinfunction "CC2_B5") (pintype "bidirectional"))
    )
    (net (code "60") (name "VIN") (class "Default")
      (node (ref "C1") (pin "1") (pinfunction "1_1") (pintype "passive"))
      (node (ref "D1") (pin "C") (pinfunction "C_C") (pintype "passive"))
      (node (ref "D5") (pin "C") (pinfunction "C_C") (pintype "passive"))
      (node (ref "Q2") (pin "2") (pinfunction "S_2") (pintype "bidirectional"))
      (node (ref "R3") (pin "2") (pinfunction "2_2") (pintype "passive"))
      (node (ref "S4") (pin "3") (pinfunction "3_3") (pintype "bidirectional"))
      (node (ref "S4") (pin "6") (pinfunction "6_6") (pintype "bidirectional"))
      (node (ref "U2") (pin "3") (pinfunction "VIN_3") (pintype "bidirectional"))
    )
    (net (code "61") (name "VIN_R3") (class "Default")
      (node (ref "B1") (pin "VIN") (pinfunction "VIN_VIN") (pintype "bidirectional"))
      (node (ref "D8") (pin "C") (pinfunction "C_C") (pintype "passive"))
    )
    (net (code "62") (name "V_USB") (class "Default")
      (node (ref "D5") (pin "A") (pinfunction "A_A") (pintype "passive"))
      (node (ref "U5") (pin "5") (pinfunction "VCC_5") (pintype "bidirectional"))
      (node (ref "UART") (pin "VBUS1") (pinfunction "VBUS_VBUS1") (pintype "bidirectional"))
      (node (ref "UART") (pin "VBUS2") (pinfunction "VBUS_VBUS2") (pintype "bidirectional"))
    )
    (net (code "63") (name "V_USB_2") (class "Default")
      (node (ref "D1") (pin "A") (pinfunction "A_A") (pintype "passive"))
      (node (ref "DIRECT_USB") (pin "VBUS1") (pinfunction "VBUS_VBUS1") (pintype "bidirectional"))
      (node (ref "DIRECT_USB") (pin "VBUS2") (pinfunction "VBUS_VBUS2") (pintype "bidirectional"))
      (node (ref "U3") (pin "5") (pinfunction "VCC_5") (pintype "bidirectional"))
    )
    (net (code "64") (name "XBEE_D+{slash}SDA") (class "Default")
      (node (ref "J2") (pin "7") (pinfunction "D+/SDA/DIO11_7") (pintype "bidirectional"))
      (node (ref "U1") (pin "4") (pinfunction "D+_4") (pintype "bidirectional"))
    )
    (net (code "65") (name "XBEE_D-") (class "Default")
      (node (ref "J2") (pin "8") (pinfunction "D-_8") (pintype "bidirectional"))
      (node (ref "U1") (pin "6") (pinfunction "D-_6") (pintype "bidirectional"))
    )
    (net (code "66") (name "unconnected-(B1-*D3-PadD3)") (class "Default")
      (node (ref "B1") (pin "D3") (pinfunction "*D3_D3") (pintype "bidirectional"))
    )
    (net (code "67") (name "unconnected-(B1-*D5-PadD5)") (class "Default")
      (node (ref "B1") (pin "D5") (pinfunction "*D5_D5") (pintype "bidirectional"))
    )
    (net (code "68") (name "unconnected-(B1-*D6-PadD6)") (class "Default")
      (node (ref "B1") (pin "D6") (pinfunction "*D6_D6") (pintype "bidirectional"))
    )
    (net (code "69") (name "unconnected-(B1-*D9-PadD9)") (class "Default")
      (node (ref "B1") (pin "D9") (pinfunction "*D9_D9") (pintype "bidirectional"))
    )
    (net (code "70") (name "unconnected-(B1-*D10-PadD10)") (class "Default")
      (node (ref "B1") (pin "D10") (pinfunction "*D10_D10") (pintype "bidirectional"))
    )
    (net (code "71") (name "unconnected-(B1-*D11-PadD11)") (class "Default")
      (node (ref "B1") (pin "D11") (pinfunction "*D11_D11") (pintype "bidirectional"))
    )
    (net (code "72") (name "unconnected-(B1-PadA0)") (class "Default")
      (node (ref "B1") (pin "A0") (pinfunction "A0_A0") (pintype "bidirectional"))
    )
    (net (code "73") (name "unconnected-(B1-PadA1)") (class "Default")
      (node (ref "B1") (pin "A1") (pinfunction "A1_A1") (pintype "bidirectional"))
    )
    (net (code "74") (name "unconnected-(B1-PadA2)") (class "Default")
      (node (ref "B1") (pin "A2") (pinfunction "A2_A2") (pintype "bidirectional"))
    )
    (net (code "75") (name "unconnected-(B1-PadA3)") (class "Default")
      (node (ref "B1") (pin "A3") (pinfunction "A3_A3") (pintype "bidirectional"))
    )
    (net (code "76") (name "unconnected-(B1-PadA4)") (class "Default")
      (node (ref "B1") (pin "A4") (pinfunction "A4_A4") (pintype "bidirectional"))
    )
    (net (code "77") (name "unconnected-(B1-PadA5)") (class "Default")
      (node (ref "B1") (pin "A5") (pinfunction "A5_A5") (pintype "bidirectional"))
    )
    (net (code "78") (name "unconnected-(B1-PadAREF)") (class "Default")
      (node (ref "B1") (pin "AREF") (pinfunction "AREF_AREF") (pintype "bidirectional"))
    )
    (net (code "79") (name "unconnected-(B1-PadD2)") (class "Default")
      (node (ref "B1") (pin "D2") (pinfunction "D2_D2") (pintype "bidirectional"))
    )
    (net (code "80") (name "unconnected-(B1-PadD4)") (class "Default")
      (node (ref "B1") (pin "D4") (pinfunction "D4_D4") (pintype "bidirectional"))
    )
    (net (code "81") (name "unconnected-(B1-PadD7)") (class "Default")
      (node (ref "B1") (pin "D7") (pinfunction "D7_D7") (pintype "bidirectional"))
    )
    (net (code "82") (name "unconnected-(B1-PadD8)") (class "Default")
      (node (ref "B1") (pin "D8") (pinfunction "D8_D8") (pintype "bidirectional"))
    )
    (net (code "83") (name "unconnected-(B1-PadIOREF)") (class "Default")
      (node (ref "B1") (pin "IOREF") (pinfunction "IOREF_IOREF") (pintype "bidirectional"))
    )
    (net (code "84") (name "unconnected-(B1-PadRES)") (class "Default")
      (node (ref "B1") (pin "RES") (pinfunction "RES_RES") (pintype "bidirectional"))
    )
    (net (code "85") (name "unconnected-(J5-Pad7)") (class "Default")
      (node (ref "J5") (pin "7") (pinfunction "7_7") (pintype "passive"))
    )
    (net (code "86") (name "unconnected-(J6-Pad8)") (class "Default")
      (node (ref "J6") (pin "8") (pinfunction "8_8") (pintype "passive"))
    )
    (net (code "87") (name "unconnected-(U1-D1--Pad8)") (class "Default")
      (node (ref "U1") (pin "8") (pinfunction "D1-_8") (pintype "bidirectional"))
    )
    (net (code "88") (name "unconnected-(U3-IO1-Pad1)") (class "Default")
      (node (ref "U3") (pin "1") (pinfunction "IO1_1") (pintype "bidirectional"))
    )
    (net (code "89") (name "unconnected-(U3-IO2-Pad3)") (class "Default")
      (node (ref "U3") (pin "3") (pinfunction "IO2_3") (pintype "bidirectional"))
    )
    (net (code "90") (name "unconnected-(U4-CBUS0-Pad18)") (class "Default")
      (node (ref "U4") (pin "18") (pinfunction "CBUS0_18") (pintype "bidirectional"))
    )
    (net (code "91") (name "unconnected-(U4-CBUS1-Pad17)") (class "Default")
      (node (ref "U4") (pin "17") (pinfunction "CBUS1_17") (pintype "bidirectional"))
    )
    (net (code "92") (name "unconnected-(U4-CBUS2-Pad10)") (class "Default")
      (node (ref "U4") (pin "10") (pinfunction "CBUS2_10") (pintype "bidirectional"))
    )
    (net (code "93") (name "unconnected-(U4-CBUS3-Pad19)") (class "Default")
      (node (ref "U4") (pin "19") (pinfunction "CBUS3_19") (pintype "bidirectional"))
    )
    (net (code "94") (name "unconnected-(U4-~{DCD}-Pad8)") (class "Default")
      (node (ref "U4") (pin "8") (pinfunction "~{DCD}_8") (pintype "bidirectional"))
    )
    (net (code "95") (name "unconnected-(U4-~{DSR}-Pad7)") (class "Default")
      (node (ref "U4") (pin "7") (pinfunction "~{DSR}_7") (pintype "bidirectional"))
    )
    (net (code "96") (name "unconnected-(U4-~{RI}-Pad5)") (class "Default")
      (node (ref "U4") (pin "5") (pinfunction "~{RI}_5") (pintype "bidirectional"))
    )
    (net (code "97") (name "unconnected-(U5-IO1-Pad1)") (class "Default")
      (node (ref "U5") (pin "1") (pinfunction "IO1_1") (pintype "bidirectional"))
    )
    (net (code "98") (name "unconnected-(U5-IO2-Pad3)") (class "Default")
      (node (ref "U5") (pin "3") (pinfunction "IO2_3") (pintype "bidirectional"))
    )
  )
)
